# GPIB-Arduino_DoubleSide.net
KiCad netlist of a schematic drawn in EAGLE
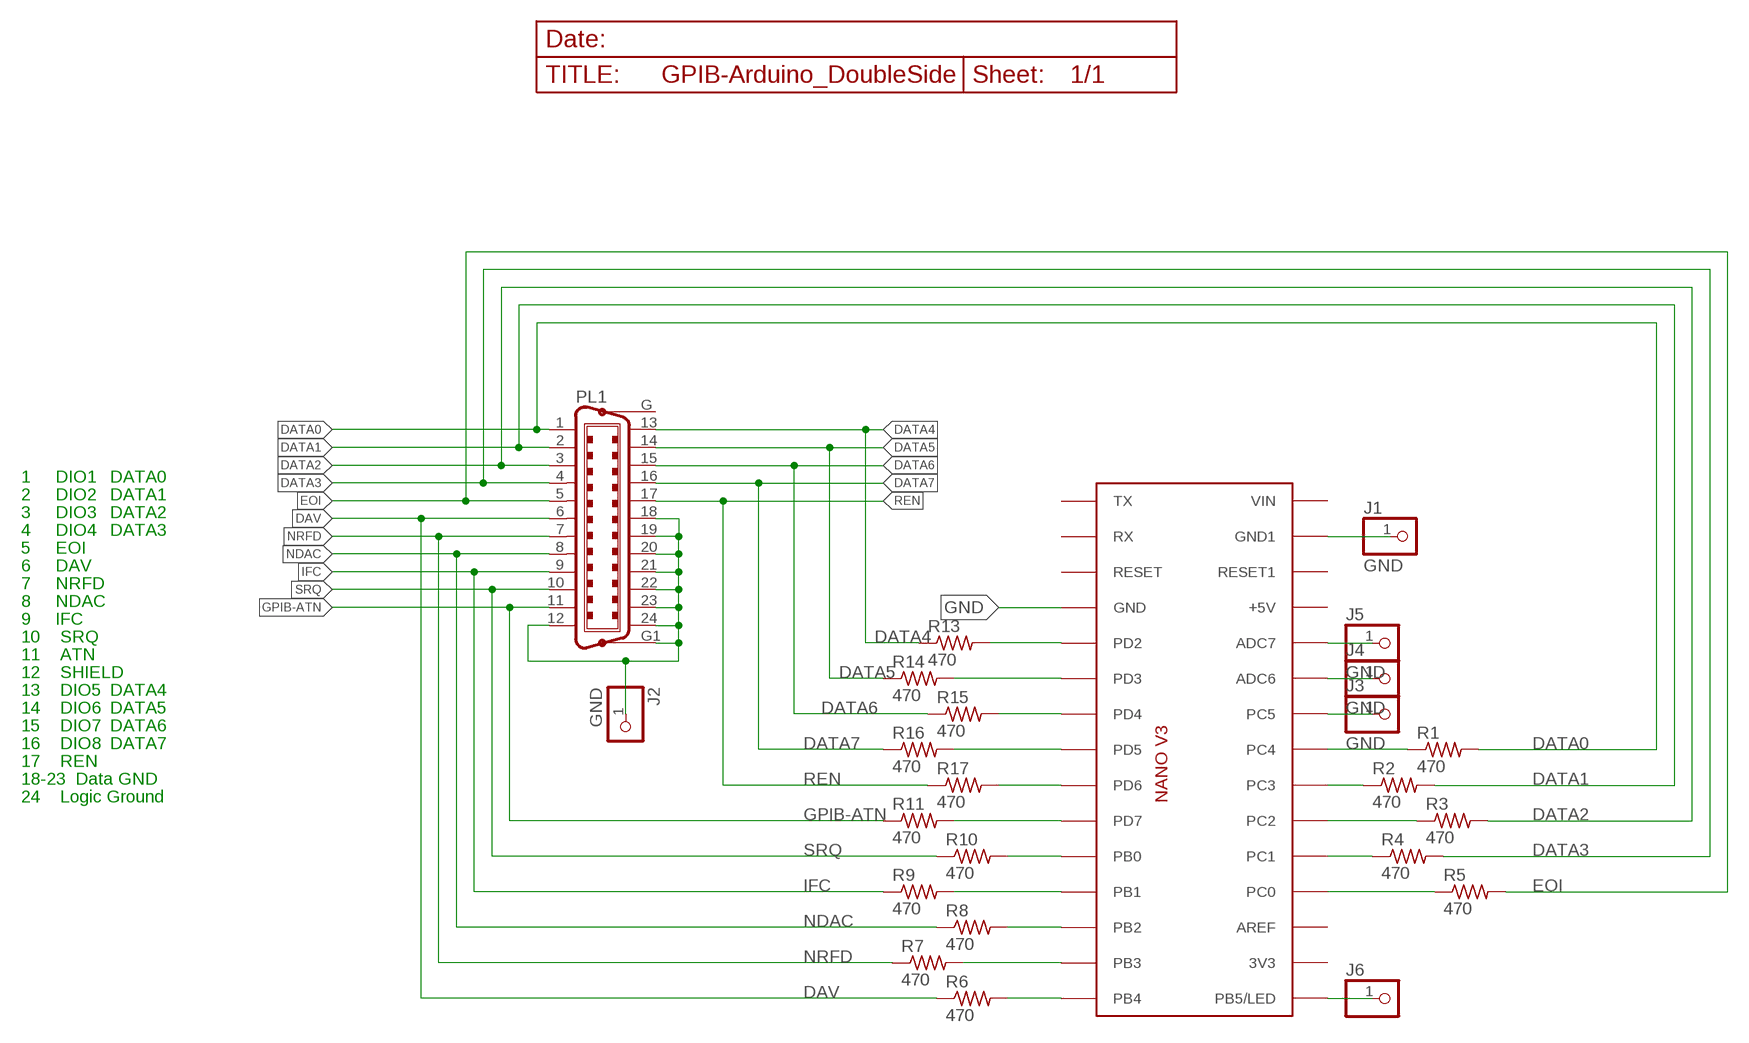
[diagram p0: schematic, sheet 1]

(export (version "E")
  (design (tool "Eeschema 10.0.6"))
  (components
    (comp (ref "J1")
      (value "GND")
      (footprint "eagle-import:1X01_ROUND")
      (libsource (lib "eagle-import") (part "PINHD1X01ROUND"))
    )
    (comp (ref "J2")
      (value "GND")
      (footprint "eagle-import:1X01_ROUND")
      (libsource (lib "eagle-import") (part "PINHD1X01ROUND"))
    )
    (comp (ref "J3")
      (value "GND")
      (footprint "eagle-import:1X01_ROUND")
      (libsource (lib "eagle-import") (part "PINHD1X01ROUND"))
    )
    (comp (ref "J4")
      (value "GND")
      (footprint "eagle-import:1X01_ROUND")
      (libsource (lib "eagle-import") (part "PINHD1X01ROUND"))
    )
    (comp (ref "J5")
      (value "GND")
      (footprint "eagle-import:1X01_ROUND")
      (libsource (lib "eagle-import") (part "PINHD1X01ROUND"))
    )
    (comp (ref "J6")
      (value "PINHD1X01ROUND")
      (footprint "eagle-import:1X01_ROUND")
      (libsource (lib "eagle-import") (part "PINHD1X01ROUND"))
    )
    (comp (ref "PL1")
      (value "C24HP")
      (footprint "eagle-import:24HP")
      (libsource (lib "eagle-import") (part "C24HP"))
    )
    (comp (ref "R1")
      (value "470")
      (footprint "eagle-import:R-1_8W")
      (libsource (lib "eagle-import") (part "R-USR-1/8W"))
    )
    (comp (ref "R2")
      (value "470")
      (footprint "eagle-import:R-1_8W")
      (libsource (lib "eagle-import") (part "R-USR-1/8W"))
    )
    (comp (ref "R3")
      (value "470")
      (footprint "eagle-import:R-1_8W")
      (libsource (lib "eagle-import") (part "R-USR-1/8W"))
    )
    (comp (ref "R4")
      (value "470")
      (footprint "eagle-import:R-1_8W")
      (libsource (lib "eagle-import") (part "R-USR-1/8W"))
    )
    (comp (ref "R5")
      (value "470")
      (footprint "eagle-import:R-1_8W")
      (libsource (lib "eagle-import") (part "R-USR-1/8W"))
    )
    (comp (ref "R6")
      (value "470")
      (footprint "eagle-import:R-1_8W")
      (libsource (lib "eagle-import") (part "R-USR-1/8W"))
    )
    (comp (ref "R7")
      (value "470")
      (footprint "eagle-import:R-1_8W")
      (libsource (lib "eagle-import") (part "R-USR-1/8W"))
    )
    (comp (ref "R8")
      (value "470")
      (footprint "eagle-import:R-1_8W")
      (libsource (lib "eagle-import") (part "R-USR-1/8W"))
    )
    (comp (ref "R9")
      (value "470")
      (footprint "eagle-import:R-1_8W")
      (libsource (lib "eagle-import") (part "R-USR-1/8W"))
    )
    (comp (ref "R10")
      (value "470")
      (footprint "eagle-import:R-1_8W")
      (libsource (lib "eagle-import") (part "R-USR-1/8W"))
    )
    (comp (ref "R11")
      (value "470")
      (footprint "eagle-import:R-1_8W")
      (libsource (lib "eagle-import") (part "R-USR-1/8W"))
    )
    (comp (ref "R13")
      (value "470")
      (footprint "eagle-import:R-1_8W")
      (libsource (lib "eagle-import") (part "R-USR-1/8W"))
    )
    (comp (ref "R14")
      (value "470")
      (footprint "eagle-import:R-1_8W")
      (libsource (lib "eagle-import") (part "R-USR-1/8W"))
    )
    (comp (ref "R15")
      (value "470")
      (footprint "eagle-import:R-1_8W")
      (libsource (lib "eagle-import") (part "R-USR-1/8W"))
    )
    (comp (ref "R16")
      (value "470")
      (footprint "eagle-import:R-1_8W")
      (libsource (lib "eagle-import") (part "R-USR-1/8W"))
    )
    (comp (ref "R17")
      (value "470")
      (footprint "eagle-import:R-1_8W")
      (libsource (lib "eagle-import") (part "R-USR-1/8W"))
    )
    (comp (ref "U$6")
      (value "ARDUINONANO")
      (footprint "eagle-import:PDIP-32")
      (libsource (lib "eagle-import") (part "ARDUINONANO"))
    )
  )
  (nets
    (net (code "1") (name "DATA0") (class "Default")
      (node (ref "PL1") (pin "1") (pinfunction "1_1") (pintype "passive"))
      (node (ref "R1") (pin "2") (pinfunction "2_2") (pintype "passive"))
    )
    (net (code "2") (name "DATA1") (class "Default")
      (node (ref "PL1") (pin "2") (pinfunction "2_2") (pintype "passive"))
      (node (ref "R2") (pin "2") (pinfunction "2_2") (pintype "passive"))
    )
    (net (code "3") (name "DATA2") (class "Default")
      (node (ref "PL1") (pin "3") (pinfunction "3_3") (pintype "passive"))
      (node (ref "R3") (pin "2") (pinfunction "2_2") (pintype "passive"))
    )
    (net (code "4") (name "DATA3") (class "Default")
      (node (ref "PL1") (pin "4") (pinfunction "4_4") (pintype "passive"))
      (node (ref "R4") (pin "2") (pinfunction "2_2") (pintype "passive"))
    )
    (net (code "5") (name "DATA4") (class "Default")
      (node (ref "PL1") (pin "13") (pinfunction "13_13") (pintype "passive"))
      (node (ref "R13") (pin "1") (pinfunction "1_1") (pintype "passive"))
    )
    (net (code "6") (name "DATA5") (class "Default")
      (node (ref "PL1") (pin "14") (pinfunction "14_14") (pintype "passive"))
      (node (ref "R14") (pin "1") (pinfunction "1_1") (pintype "passive"))
    )
    (net (code "7") (name "DATA6") (class "Default")
      (node (ref "PL1") (pin "15") (pinfunction "15_15") (pintype "passive"))
      (node (ref "R15") (pin "1") (pinfunction "1_1") (pintype "passive"))
    )
    (net (code "8") (name "DATA7") (class "Default")
      (node (ref "PL1") (pin "16") (pinfunction "16_16") (pintype "passive"))
      (node (ref "R16") (pin "1") (pinfunction "1_1") (pintype "passive"))
    )
    (net (code "9") (name "DAV") (class "Default")
      (node (ref "PL1") (pin "6") (pinfunction "6_6") (pintype "passive"))
      (node (ref "R6") (pin "1") (pinfunction "1_1") (pintype "passive"))
    )
    (net (code "10") (name "EOI") (class "Default")
      (node (ref "PL1") (pin "5") (pinfunction "5_5") (pintype "passive"))
      (node (ref "R5") (pin "2") (pinfunction "2_2") (pintype "passive"))
    )
    (net (code "11") (name "GND") (class "Default")
      (node (ref "J1") (pin "1") (pinfunction "1_1") (pintype "passive"))
      (node (ref "J2") (pin "1") (pinfunction "1_1") (pintype "passive"))
      (node (ref "PL1") (pin "12") (pinfunction "12_12") (pintype "passive"))
      (node (ref "PL1") (pin "18") (pinfunction "18_18") (pintype "passive"))
      (node (ref "PL1") (pin "19") (pinfunction "19_19") (pintype "passive"))
      (node (ref "PL1") (pin "20") (pinfunction "20_20") (pintype "passive"))
      (node (ref "PL1") (pin "21") (pinfunction "21_21") (pintype "passive"))
      (node (ref "PL1") (pin "22") (pinfunction "22_22") (pintype "passive"))
      (node (ref "PL1") (pin "23") (pinfunction "23_23") (pintype "passive"))
      (node (ref "PL1") (pin "24") (pinfunction "24_24") (pintype "passive"))
      (node (ref "PL1") (pin "G1") (pinfunction "G1_G1") (pintype "passive"))
      (node (ref "U$6") (pin "GND") (pinfunction "GND_GND") (pintype "bidirectional"))
      (node (ref "U$6") (pin "GND1") (pinfunction "GND1_GND1") (pintype "bidirectional"))
    )
    (net (code "12") (name "GPIB-ATN") (class "Default")
      (node (ref "PL1") (pin "11") (pinfunction "11_11") (pintype "passive"))
      (node (ref "R11") (pin "1") (pinfunction "1_1") (pintype "passive"))
    )
    (net (code "13") (name "IFC") (class "Default")
      (node (ref "PL1") (pin "9") (pinfunction "9_9") (pintype "passive"))
      (node (ref "R9") (pin "1") (pinfunction "1_1") (pintype "passive"))
    )
    (net (code "14") (name "NDAC") (class "Default")
      (node (ref "PL1") (pin "8") (pinfunction "8_8") (pintype "passive"))
      (node (ref "R8") (pin "1") (pinfunction "1_1") (pintype "passive"))
    )
    (net (code "15") (name "NRFD") (class "Default")
      (node (ref "PL1") (pin "7") (pinfunction "7_7") (pintype "passive"))
      (node (ref "R7") (pin "1") (pinfunction "1_1") (pintype "passive"))
    )
    (net (code "16") (name "Net-(U$6-ADC6)") (class "Default")
      (node (ref "J4") (pin "1") (pinfunction "1_1") (pintype "passive"))
      (node (ref "U$6") (pin "A1") (pinfunction "ADC6_A1") (pintype "bidirectional"))
    )
    (net (code "17") (name "Net-(U$6-ADC7)") (class "Default")
      (node (ref "J5") (pin "1") (pinfunction "1_1") (pintype "passive"))
      (node (ref "U$6") (pin "A0") (pinfunction "ADC7_A0") (pintype "bidirectional"))
    )
    (net (code "18") (name "Net-(U$6-PB0)") (class "Default")
      (node (ref "R10") (pin "2") (pinfunction "2_2") (pintype "passive"))
      (node (ref "U$6") (pin "D8") (pinfunction "PB0_D8") (pintype "bidirectional"))
    )
    (net (code "19") (name "Net-(U$6-PB1)") (class "Default")
      (node (ref "R9") (pin "2") (pinfunction "2_2") (pintype "passive"))
      (node (ref "U$6") (pin "D9") (pinfunction "PB1_D9") (pintype "bidirectional"))
    )
    (net (code "20") (name "Net-(U$6-PB2)") (class "Default")
      (node (ref "R8") (pin "2") (pinfunction "2_2") (pintype "passive"))
      (node (ref "U$6") (pin "D10") (pinfunction "PB2_D10") (pintype "bidirectional"))
    )
    (net (code "21") (name "Net-(U$6-PB3)") (class "Default")
      (node (ref "R7") (pin "2") (pinfunction "2_2") (pintype "passive"))
      (node (ref "U$6") (pin "D11") (pinfunction "PB3_D11") (pintype "bidirectional"))
    )
    (net (code "22") (name "Net-(U$6-PB4)") (class "Default")
      (node (ref "R6") (pin "2") (pinfunction "2_2") (pintype "passive"))
      (node (ref "U$6") (pin "D12") (pinfunction "PB4_D12") (pintype "bidirectional"))
    )
    (net (code "23") (name "Net-(U$6-PB5{slash}LED)") (class "Default")
      (node (ref "J6") (pin "1") (pinfunction "1_1") (pintype "passive"))
      (node (ref "U$6") (pin "D13") (pinfunction "PB5/LED_D13") (pintype "bidirectional"))
    )
    (net (code "24") (name "Net-(U$6-PC0)") (class "Default")
      (node (ref "R5") (pin "1") (pinfunction "1_1") (pintype "passive"))
      (node (ref "U$6") (pin "A7") (pinfunction "PC0_A7") (pintype "bidirectional"))
    )
    (net (code "25") (name "Net-(U$6-PC1)") (class "Default")
      (node (ref "R4") (pin "1") (pinfunction "1_1") (pintype "passive"))
      (node (ref "U$6") (pin "A6") (pinfunction "PC1_A6") (pintype "bidirectional"))
    )
    (net (code "26") (name "Net-(U$6-PC2)") (class "Default")
      (node (ref "R3") (pin "1") (pinfunction "1_1") (pintype "passive"))
      (node (ref "U$6") (pin "A5") (pinfunction "PC2_A5") (pintype "bidirectional"))
    )
    (net (code "27") (name "Net-(U$6-PC3)") (class "Default")
      (node (ref "R2") (pin "1") (pinfunction "1_1") (pintype "passive"))
      (node (ref "U$6") (pin "A4") (pinfunction "PC3_A4") (pintype "bidirectional"))
    )
    (net (code "28") (name "Net-(U$6-PC4)") (class "Default")
      (node (ref "R1") (pin "1") (pinfunction "1_1") (pintype "passive"))
      (node (ref "U$6") (pin "A3") (pinfunction "PC4_A3") (pintype "bidirectional"))
    )
    (net (code "29") (name "Net-(U$6-PC5)") (class "Default")
      (node (ref "J3") (pin "1") (pinfunction "1_1") (pintype "passive"))
      (node (ref "U$6") (pin "A2") (pinfunction "PC5_A2") (pintype "bidirectional"))
    )
    (net (code "30") (name "Net-(U$6-PD2)") (class "Default")
      (node (ref "R13") (pin "2") (pinfunction "2_2") (pintype "passive"))
      (node (ref "U$6") (pin "D2") (pinfunction "PD2_D2") (pintype "bidirectional"))
    )
    (net (code "31") (name "Net-(U$6-PD3)") (class "Default")
      (node (ref "R14") (pin "2") (pinfunction "2_2") (pintype "passive"))
      (node (ref "U$6") (pin "D3") (pinfunction "PD3_D3") (pintype "bidirectional"))
    )
    (net (code "32") (name "Net-(U$6-PD4)") (class "Default")
      (node (ref "R15") (pin "2") (pinfunction "2_2") (pintype "passive"))
      (node (ref "U$6") (pin "D4") (pinfunction "PD4_D4") (pintype "bidirectional"))
    )
    (net (code "33") (name "Net-(U$6-PD5)") (class "Default")
      (node (ref "R16") (pin "2") (pinfunction "2_2") (pintype "passive"))
      (node (ref "U$6") (pin "D5") (pinfunction "PD5_D5") (pintype "bidirectional"))
    )
    (net (code "34") (name "Net-(U$6-PD6)") (class "Default")
      (node (ref "R17") (pin "2") (pinfunction "2_2") (pintype "passive"))
      (node (ref "U$6") (pin "D6") (pinfunction "PD6_D6") (pintype "bidirectional"))
    )
    (net (code "35") (name "Net-(U$6-PD7)") (class "Default")
      (node (ref "R11") (pin "2") (pinfunction "2_2") (pintype "passive"))
      (node (ref "U$6") (pin "D7") (pinfunction "PD7_D7") (pintype "bidirectional"))
    )
    (net (code "36") (name "REN") (class "Default")
      (node (ref "PL1") (pin "17") (pinfunction "17_17") (pintype "passive"))
      (node (ref "R17") (pin "1") (pinfunction "1_1") (pintype "passive"))
    )
    (net (code "37") (name "SRQ") (class "Default")
      (node (ref "PL1") (pin "10") (pinfunction "10_10") (pintype "passive"))
      (node (ref "R10") (pin "1") (pinfunction "1_1") (pintype "passive"))
    )
    (net (code "38") (name "unconnected-(PL1-PadG)") (class "Default")
      (node (ref "PL1") (pin "G") (pinfunction "G_G") (pintype "passive"))
    )
    (net (code "39") (name "unconnected-(U$6-Pad+5V)") (class "Default")
      (node (ref "U$6") (pin "+5V") (pinfunction "+5V_+5V") (pintype "bidirectional"))
    )
    (net (code "40") (name "unconnected-(U$6-Pad3V3)") (class "Default")
      (node (ref "U$6") (pin "3V3") (pinfunction "3V3_3V3") (pintype "bidirectional"))
    )
    (net (code "41") (name "unconnected-(U$6-PadAREF)") (class "Default")
      (node (ref "U$6") (pin "AREF") (pinfunction "AREF_AREF") (pintype "bidirectional"))
    )
    (net (code "42") (name "unconnected-(U$6-PadRESET)") (class "Default")
      (node (ref "U$6") (pin "RESET") (pinfunction "RESET_RESET") (pintype "bidirectional"))
    )
    (net (code "43") (name "unconnected-(U$6-PadRESET1)") (class "Default")
      (node (ref "U$6") (pin "RESET1") (pinfunction "RESET1_RESET1") (pintype "bidirectional"))
    )
    (net (code "44") (name "unconnected-(U$6-PadVIN)") (class "Default")
      (node (ref "U$6") (pin "VIN") (pinfunction "VIN_VIN") (pintype "bidirectional"))
    )
    (net (code "45") (name "unconnected-(U$6-RX-PadD0{slash}RX)") (class "Default")
      (node (ref "U$6") (pin "D0/RX") (pinfunction "RX_D0/RX") (pintype "bidirectional"))
    )
    (net (code "46") (name "unconnected-(U$6-TX-PadD1{slash}TX)") (class "Default")
      (node (ref "U$6") (pin "D1/TX") (pinfunction "TX_D1/TX") (pintype "bidirectional"))
    )
  )
)
